# sensorBox.net
KiCad netlist of a schematic drawn in EAGLE
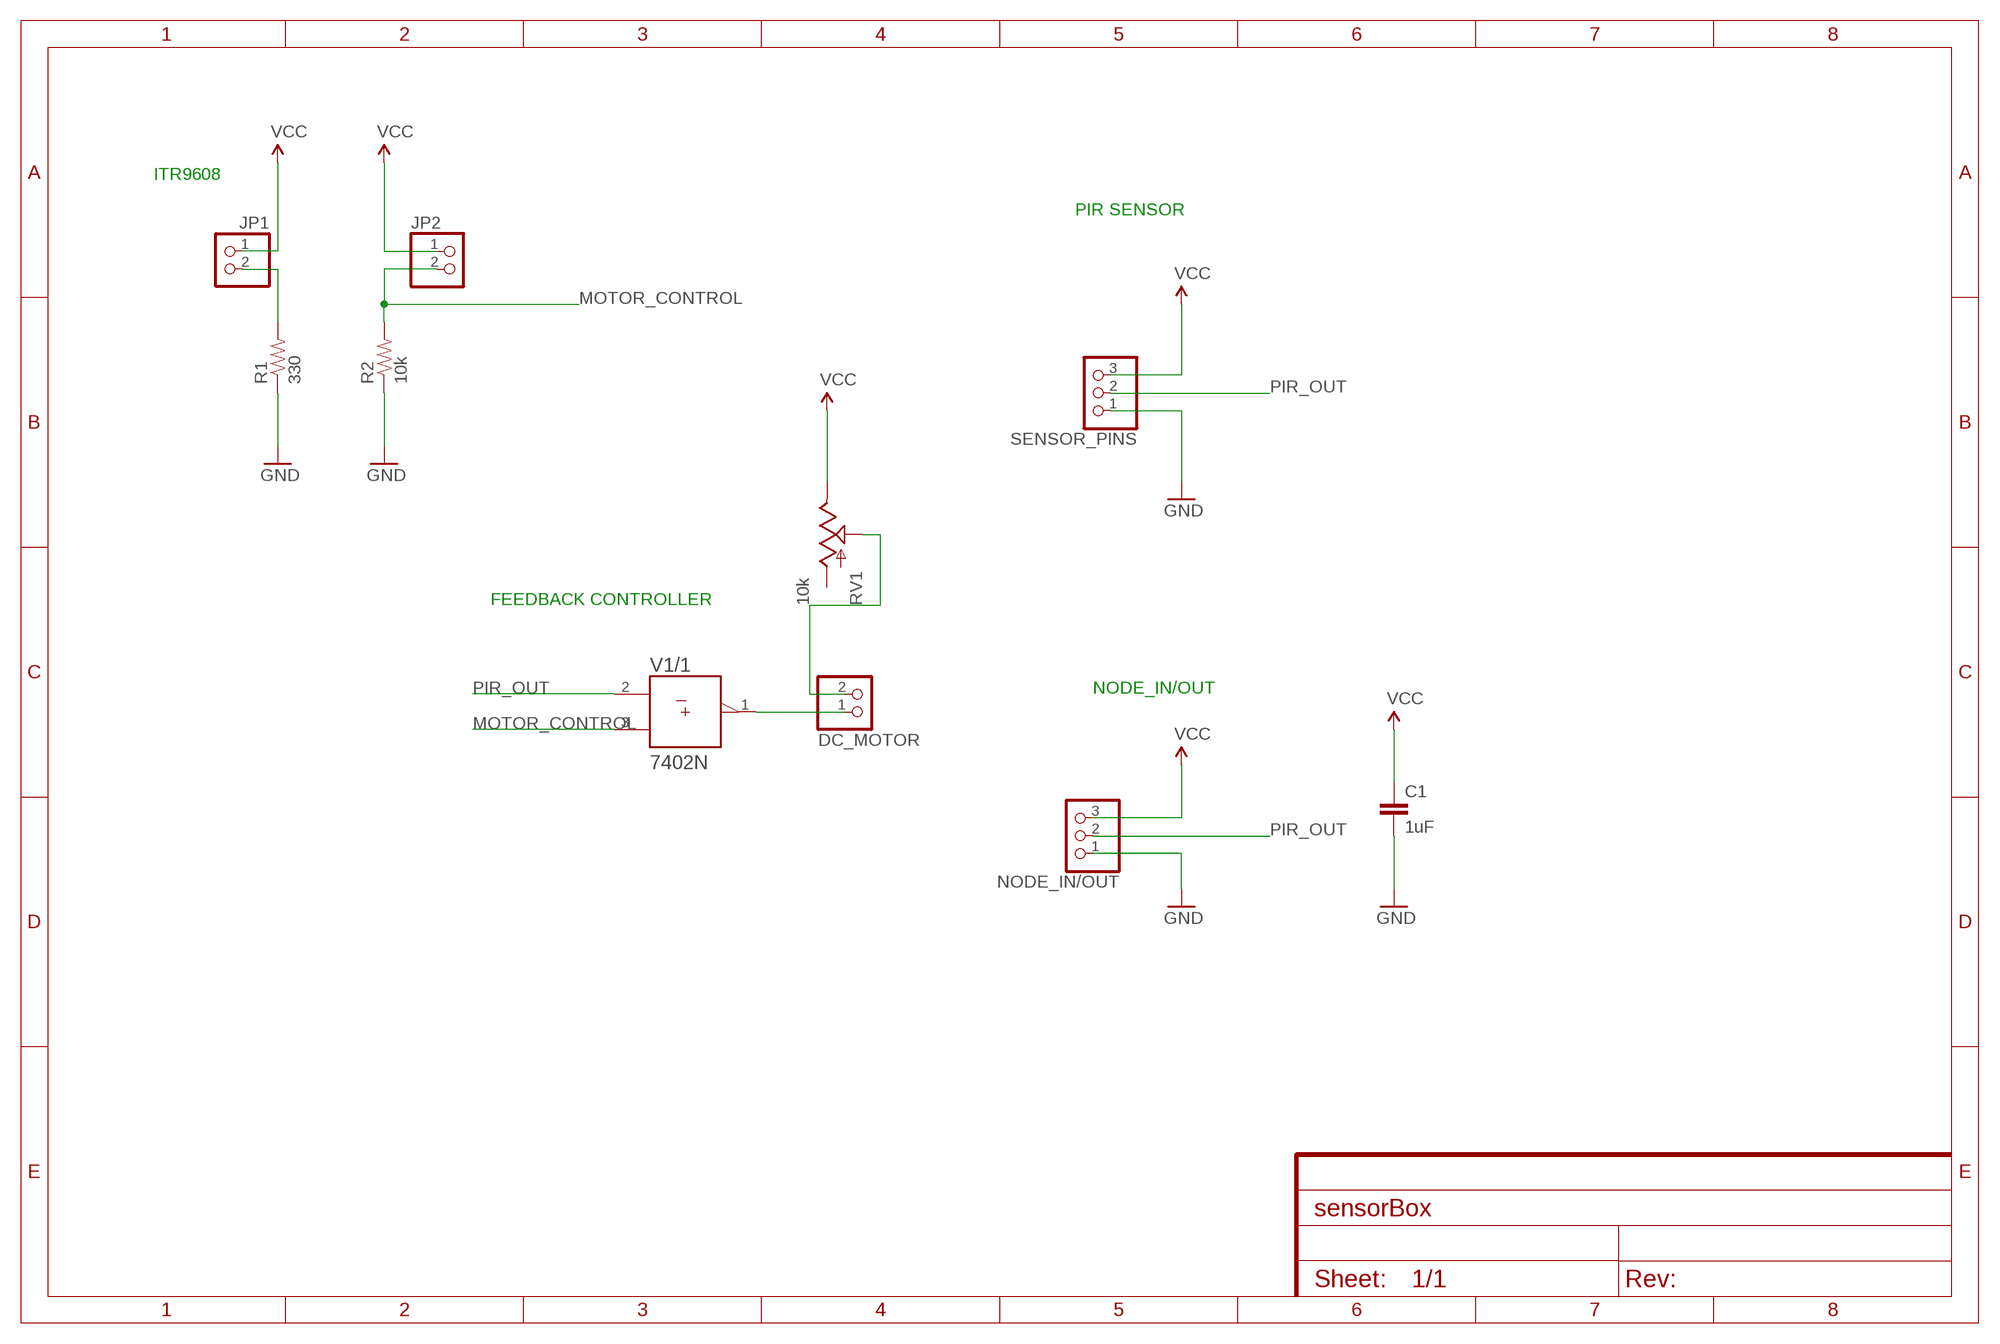
[diagram p0: schematic, sheet 1]

(export (version "E")
  (design (tool "Eeschema 10.0.6"))
  (components
    (comp (ref "C1")
      (value "1uF")
      (footprint "eagle-import:CAP-PTH-SMALL")
      (libsource (lib "eagle-import") (part "CAPPTH"))
    )
    (comp (ref "DC_MOTOR")
      (value "PINHD-1X2")
      (footprint "eagle-import:1X02")
      (libsource (lib "eagle-import") (part "PINHD-1X2"))
    )
    (comp (ref "JP1")
      (value "PINHD-1X2")
      (footprint "eagle-import:1X02")
      (libsource (lib "eagle-import") (part "PINHD-1X2"))
    )
    (comp (ref "JP2")
      (value "PINHD-1X2")
      (footprint "eagle-import:1X02")
      (libsource (lib "eagle-import") (part "PINHD-1X2"))
    )
    (comp (ref "NODE_IN/OUT")
      (value "PINHD-1X3")
      (footprint "eagle-import:1X03")
      (libsource (lib "eagle-import") (part "PINHD-1X3"))
    )
    (comp (ref "R1")
      (value "330")
      (footprint "eagle-import:AXIAL-0.4")
      (libsource (lib "eagle-import") (part "RESISTORPTH-1/4W"))
    )
    (comp (ref "R2")
      (value "10k")
      (footprint "eagle-import:AXIAL-0.4")
      (libsource (lib "eagle-import") (part "RESISTORPTH-1/4W"))
    )
    (comp (ref "RV1")
      (value "10k")
      (footprint "eagle-import:TRIM_POT")
      (libsource (lib "eagle-import") (part "POTTRIM"))
    )
    (comp (ref "SENSOR_PINS")
      (value "PINHD-1X3")
      (footprint "eagle-import:1X03")
      (libsource (lib "eagle-import") (part "PINHD-1X3"))
    )
    (comp (ref "V1")
      (value "7402N")
      (footprint "eagle-import:DIL14")
      (libsource (lib "eagle-import") (part "7402N"))
    )
  )
  (nets
    (net (code "1") (name "/MOTOR_CONTROL") (class "Default")
      (node (ref "JP2") (pin "2") (pinfunction "2_2") (pintype "passive"))
      (node (ref "R2") (pin "P$2") (pinfunction "2_P$2") (pintype "passive"))
      (node (ref "V1") (pin "3") (pinfunction "B_3") (pintype "input"))
    )
    (net (code "2") (name "/PIR_OUT") (class "Default")
      (node (ref "NODE_IN/OUT") (pin "2") (pinfunction "2_2") (pintype "passive"))
      (node (ref "SENSOR_PINS") (pin "2") (pinfunction "2_2") (pintype "passive"))
      (node (ref "V1") (pin "2") (pinfunction "A_2") (pintype "input"))
    )
    (net (code "3") (name "GND") (class "Default")
      (node (ref "C1") (pin "2") (pinfunction "2_2") (pintype "passive"))
      (node (ref "NODE_IN/OUT") (pin "1") (pinfunction "1_1") (pintype "passive"))
      (node (ref "R1") (pin "P$1") (pinfunction "1_P$1") (pintype "passive"))
      (node (ref "R2") (pin "P$1") (pinfunction "1_P$1") (pintype "passive"))
      (node (ref "SENSOR_PINS") (pin "1") (pinfunction "1_1") (pintype "passive"))
    )
    (net (code "4") (name "Net-(R1-2)") (class "Default")
      (node (ref "JP1") (pin "2") (pinfunction "2_2") (pintype "passive"))
      (node (ref "R1") (pin "P$2") (pinfunction "2_P$2") (pintype "passive"))
    )
    (net (code "5") (name "Net-(RV1-S)") (class "Default")
      (node (ref "DC_MOTOR") (pin "2") (pinfunction "2_2") (pintype "passive"))
      (node (ref "RV1") (pin "1") (pinfunction "S_1") (pintype "passive"))
    )
    (net (code "6") (name "Net-(V1C-Y)") (class "Default")
      (node (ref "DC_MOTOR") (pin "1") (pinfunction "1_1") (pintype "passive"))
      (node (ref "V1") (pin "1") (pinfunction "Y_1") (pintype "output"))
    )
    (net (code "7") (name "VCC") (class "Default")
      (node (ref "C1") (pin "1") (pinfunction "1_1") (pintype "passive"))
      (node (ref "JP1") (pin "1") (pinfunction "1_1") (pintype "passive"))
      (node (ref "JP2") (pin "1") (pinfunction "1_1") (pintype "passive"))
      (node (ref "NODE_IN/OUT") (pin "3") (pinfunction "3_3") (pintype "passive"))
      (node (ref "RV1") (pin "2") (pinfunction "E_2") (pintype "passive"))
      (node (ref "SENSOR_PINS") (pin "3") (pinfunction "3_3") (pintype "passive"))
    )
    (net (code "8") (name "unconnected-(RV1-A-Pad3)") (class "Default")
      (node (ref "RV1") (pin "3") (pinfunction "A_3") (pintype "passive"))
    )
  )
)
